# Adafruit_BNO055.net
KiCad netlist of a schematic drawn in EAGLE
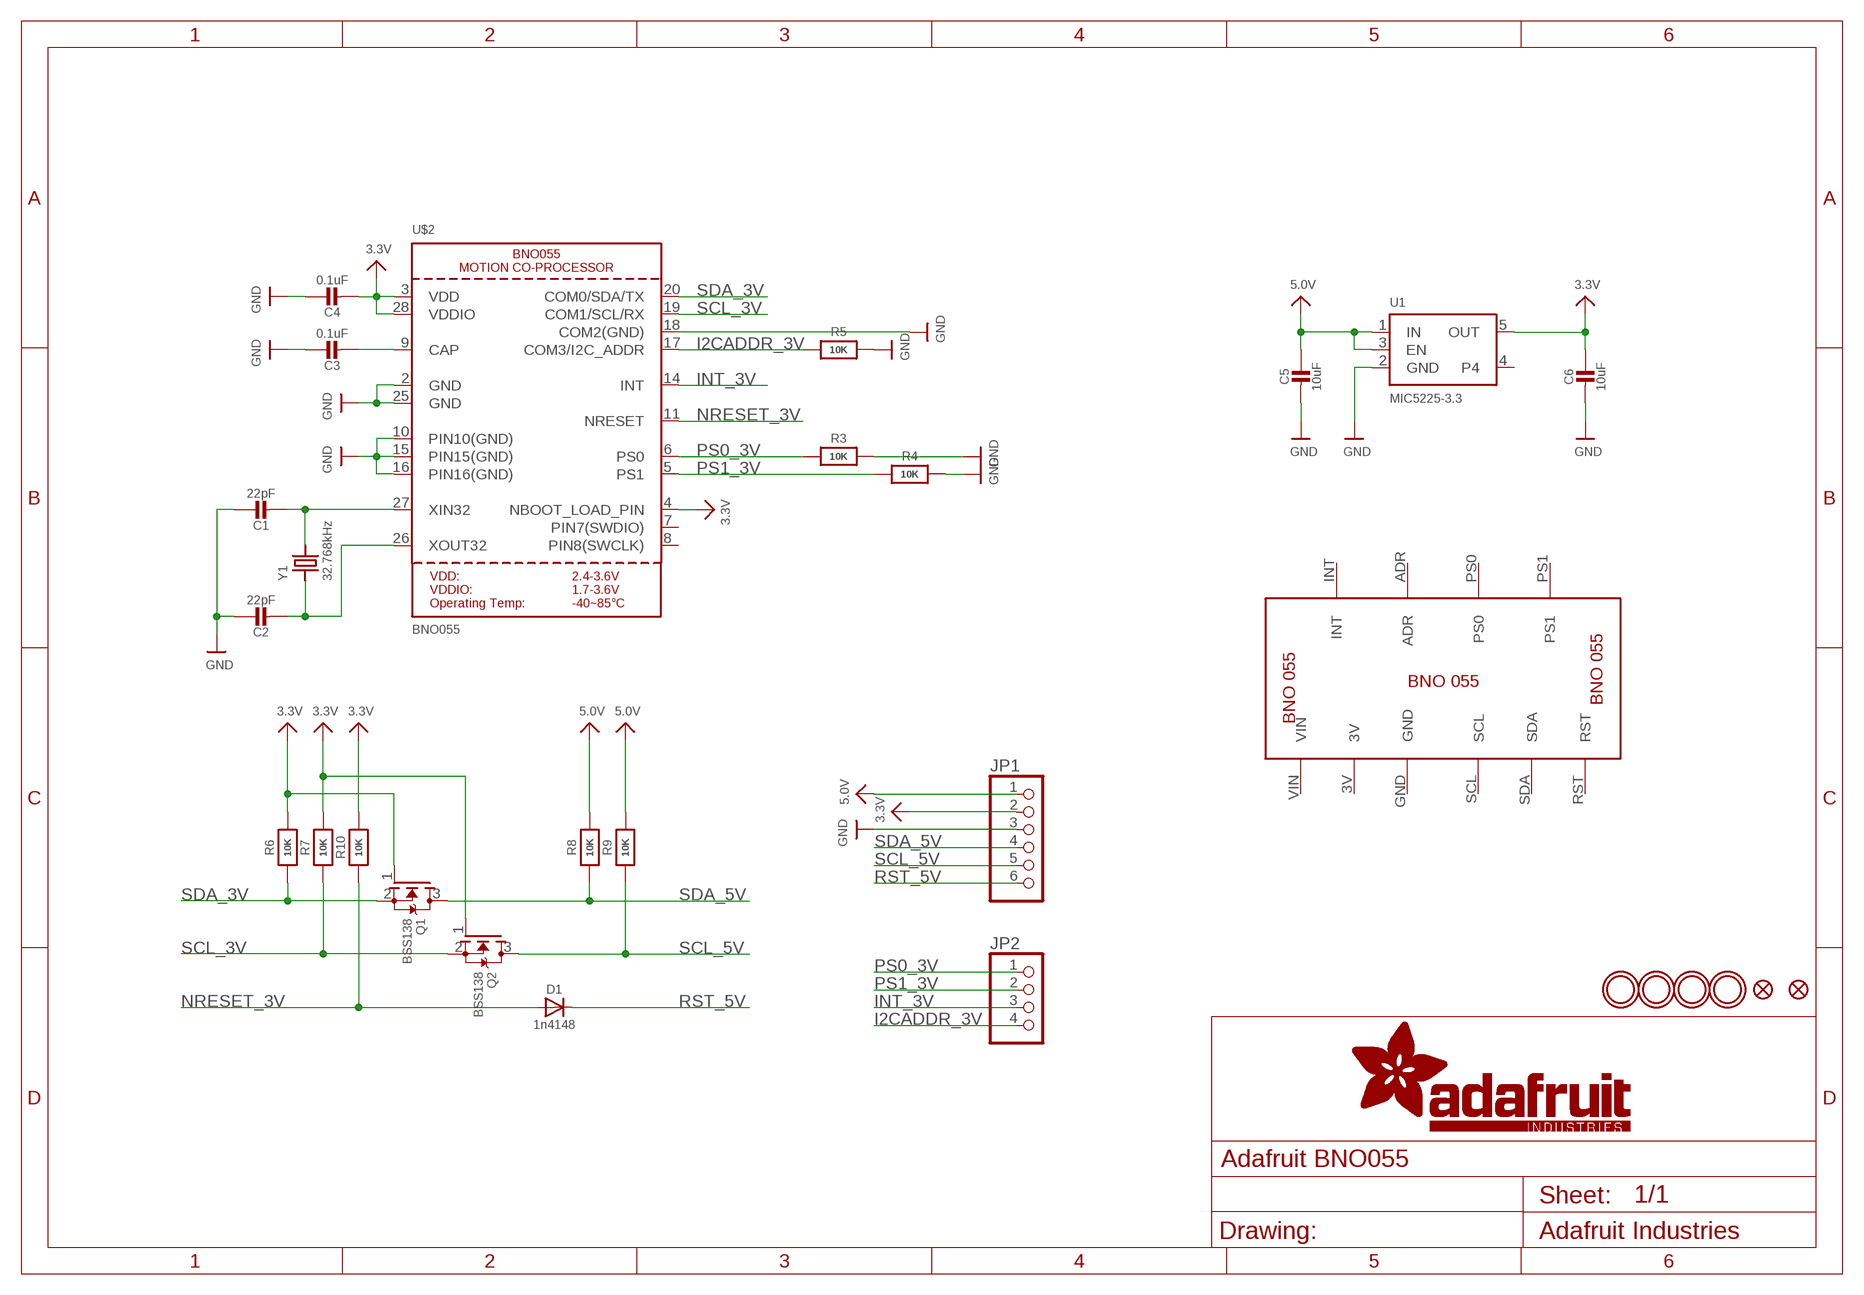
[diagram p0: schematic, sheet 1]

(export (version "E")
  (design (tool "Eeschema 10.0.6"))
  (components
    (comp (ref "C1")
      (value "22pF")
      (footprint "eagle-import:0805-NO")
      (libsource (lib "eagle-import") (part "CAP_CERAMIC0805-NOOUTLINE"))
    )
    (comp (ref "C2")
      (value "22pF")
      (footprint "eagle-import:0805-NO")
      (libsource (lib "eagle-import") (part "CAP_CERAMIC0805-NOOUTLINE"))
    )
    (comp (ref "C3")
      (value "0.1uF")
      (footprint "eagle-import:0805-NO")
      (libsource (lib "eagle-import") (part "CAP_CERAMIC0805-NOOUTLINE"))
    )
    (comp (ref "C4")
      (value "0.1uF")
      (footprint "eagle-import:0805_10MGAP")
      (libsource (lib "eagle-import") (part "CAP_CERAMIC0805_10MGAP"))
    )
    (comp (ref "C5")
      (value "10uF")
      (footprint "eagle-import:0805-NO")
      (libsource (lib "eagle-import") (part "CAP_CERAMIC0805-NOOUTLINE"))
    )
    (comp (ref "C6")
      (value "10uF")
      (footprint "eagle-import:0805_10MGAP")
      (libsource (lib "eagle-import") (part "CAP_CERAMIC0805_10MGAP"))
    )
    (comp (ref "D1")
      (value "1n4148")
      (footprint "eagle-import:SOD-323")
      (libsource (lib "eagle-import") (part "DIODESOD-323"))
    )
    (comp (ref "FID1")
      (value "FIDUCIAL\"\"")
      (footprint "eagle-import:FIDUCIAL_1MM")
      (libsource (lib "eagle-import") (part "FIDUCIAL{dblquote}{dblquote}"))
    )
    (comp (ref "FID2")
      (value "FIDUCIAL\"\"")
      (footprint "eagle-import:FIDUCIAL_1MM")
      (libsource (lib "eagle-import") (part "FIDUCIAL{dblquote}{dblquote}"))
    )
    (comp (ref "JP1")
      (value "HEADER-1X676MIL")
      (footprint "eagle-import:1X06_ROUND_76")
      (libsource (lib "eagle-import") (part "HEADER-1X676MIL"))
    )
    (comp (ref "JP2")
      (value "HEADER-1X476MIL")
      (footprint "eagle-import:1X04_ROUND_76")
      (libsource (lib "eagle-import") (part "HEADER-1X476MIL"))
    )
    (comp (ref "Q1")
      (value "BSS138")
      (footprint "eagle-import:SOT23-WIDE")
      (libsource (lib "eagle-import") (part "MOSFET-NWIDE"))
    )
    (comp (ref "Q2")
      (value "BSS138")
      (footprint "eagle-import:SOT23-WIDE")
      (libsource (lib "eagle-import") (part "MOSFET-NWIDE"))
    )
    (comp (ref "R3")
      (value "10K")
      (footprint "eagle-import:0805-NO")
      (libsource (lib "eagle-import") (part "RESISTOR0805_NOOUTLINE"))
    )
    (comp (ref "R4")
      (value "10K")
      (footprint "eagle-import:0805-NO")
      (libsource (lib "eagle-import") (part "RESISTOR0805_NOOUTLINE"))
    )
    (comp (ref "R5")
      (value "10K")
      (footprint "eagle-import:0805-NO")
      (libsource (lib "eagle-import") (part "RESISTOR0805_NOOUTLINE"))
    )
    (comp (ref "R6")
      (value "10K")
      (footprint "eagle-import:0805-NO")
      (libsource (lib "eagle-import") (part "RESISTOR0805_NOOUTLINE"))
    )
    (comp (ref "R7")
      (value "10K")
      (footprint "eagle-import:0805-NO")
      (libsource (lib "eagle-import") (part "RESISTOR0805_NOOUTLINE"))
    )
    (comp (ref "R8")
      (value "10K")
      (footprint "eagle-import:_0805MP")
      (libsource (lib "eagle-import") (part "RESISTOR_0805MP"))
    )
    (comp (ref "R9")
      (value "10K")
      (footprint "eagle-import:_0805MP")
      (libsource (lib "eagle-import") (part "RESISTOR_0805MP"))
    )
    (comp (ref "R10")
      (value "10K")
      (footprint "eagle-import:0805-NO")
      (libsource (lib "eagle-import") (part "RESISTOR0805_NOOUTLINE"))
    )
    (comp (ref "U$2")
      (value "BNO055")
      (footprint "eagle-import:BNO055")
      (libsource (lib "eagle-import") (part "microbuilder_BNO055"))
    )
    (comp (ref "U$29")
      (value "MOUNTINGHOLE2.5_THICK")
      (footprint "eagle-import:MOUNTINGHOLE_2.5_PLATED_THICK")
      (libsource (lib "eagle-import") (part "MOUNTINGHOLE2.5_THICK"))
    )
    (comp (ref "U$30")
      (value "MOUNTINGHOLE2.5_THICK")
      (footprint "eagle-import:MOUNTINGHOLE_2.5_PLATED_THICK")
      (libsource (lib "eagle-import") (part "MOUNTINGHOLE2.5_THICK"))
    )
    (comp (ref "U$31")
      (value "MOUNTINGHOLE2.5_THICK")
      (footprint "eagle-import:MOUNTINGHOLE_2.5_PLATED_THICK")
      (libsource (lib "eagle-import") (part "MOUNTINGHOLE2.5_THICK"))
    )
    (comp (ref "U$32")
      (value "MOUNTINGHOLE2.5_THICK")
      (footprint "eagle-import:MOUNTINGHOLE_2.5_PLATED_THICK")
      (libsource (lib "eagle-import") (part "MOUNTINGHOLE2.5_THICK"))
    )
    (comp (ref "U$34")
      (value "BNO055")
      (footprint "eagle-import:BNO055")
      (libsource (lib "eagle-import") (part "BNO055"))
    )
    (comp (ref "U1")
      (value "MIC5225-3.3")
      (footprint "eagle-import:SOT23-5")
      (libsource (lib "eagle-import") (part "VREG_SOT23-5"))
    )
    (comp (ref "Y1")
      (value "32.768kHz")
      (footprint "eagle-import:CRYSTAL_8X3.8")
      (libsource (lib "eagle-import") (part "CRYSTAL8.0X3.8"))
    )
  )
  (nets
    (net (code "1") (name "/I2CADDR_3V") (class "Default")
      (node (ref "JP2") (pin "4") (pinfunction "4_4") (pintype "passive"))
      (node (ref "R5") (pin "1") (pinfunction "1_1") (pintype "passive"))
      (node (ref "U$2") (pin "17") (pinfunction "COM3/I2C_ADDR_17") (pintype "bidirectional"))
    )
    (net (code "2") (name "/INT_3V") (class "Default")
      (node (ref "JP2") (pin "3") (pinfunction "3_3") (pintype "passive"))
      (node (ref "U$2") (pin "14") (pinfunction "INT_14") (pintype "output"))
    )
    (net (code "3") (name "/NRESET_3V") (class "Default")
      (node (ref "D1") (pin "A") (pinfunction "A_A") (pintype "passive"))
      (node (ref "R10") (pin "1") (pinfunction "1_1") (pintype "passive"))
      (node (ref "U$2") (pin "11") (pinfunction "NRESET_11") (pintype "bidirectional"))
    )
    (net (code "4") (name "/PS0_3V") (class "Default")
      (node (ref "JP2") (pin "1") (pinfunction "1_1") (pintype "passive"))
      (node (ref "R3") (pin "1") (pinfunction "1_1") (pintype "passive"))
      (node (ref "U$2") (pin "6") (pinfunction "PS0_6") (pintype "input"))
    )
    (net (code "5") (name "/PS1_3V") (class "Default")
      (node (ref "JP2") (pin "2") (pinfunction "2_2") (pintype "passive"))
      (node (ref "R4") (pin "1") (pinfunction "1_1") (pintype "passive"))
      (node (ref "U$2") (pin "5") (pinfunction "PS1_5") (pintype "input"))
    )
    (net (code "6") (name "/RST_5V") (class "Default")
      (node (ref "D1") (pin "C") (pinfunction "C_C") (pintype "passive"))
      (node (ref "JP1") (pin "6") (pinfunction "6_6") (pintype "passive"))
    )
    (net (code "7") (name "/SCL_3V") (class "Default")
      (node (ref "Q2") (pin "2") (pinfunction "S_2") (pintype "bidirectional"))
      (node (ref "R7") (pin "1") (pinfunction "1_1") (pintype "passive"))
      (node (ref "U$2") (pin "19") (pinfunction "COM1/SCL/RX_19") (pintype "bidirectional"))
    )
    (net (code "8") (name "/SCL_5V") (class "Default")
      (node (ref "JP1") (pin "5") (pinfunction "5_5") (pintype "passive"))
      (node (ref "Q2") (pin "3") (pinfunction "D_3") (pintype "bidirectional"))
      (node (ref "R9") (pin "1") (pinfunction "1_1") (pintype "passive"))
    )
    (net (code "9") (name "/SDA_3V") (class "Default")
      (node (ref "Q1") (pin "2") (pinfunction "S_2") (pintype "bidirectional"))
      (node (ref "R6") (pin "1") (pinfunction "1_1") (pintype "passive"))
      (node (ref "U$2") (pin "20") (pinfunction "COM0/SDA/TX_20") (pintype "bidirectional"))
    )
    (net (code "10") (name "/SDA_5V") (class "Default")
      (node (ref "JP1") (pin "4") (pinfunction "4_4") (pintype "passive"))
      (node (ref "Q1") (pin "3") (pinfunction "D_3") (pintype "bidirectional"))
      (node (ref "R8") (pin "1") (pinfunction "1_1") (pintype "passive"))
    )
    (net (code "11") (name "3.3V") (class "Default")
      (node (ref "C4") (pin "2") (pinfunction "2_2") (pintype "passive"))
      (node (ref "C6") (pin "1") (pinfunction "1_1") (pintype "passive"))
      (node (ref "JP1") (pin "2") (pinfunction "2_2") (pintype "passive"))
      (node (ref "Q1") (pin "1") (pinfunction "G_1") (pintype "bidirectional"))
      (node (ref "Q2") (pin "1") (pinfunction "G_1") (pintype "bidirectional"))
      (node (ref "R10") (pin "2") (pinfunction "2_2") (pintype "passive"))
      (node (ref "R6") (pin "2") (pinfunction "2_2") (pintype "passive"))
      (node (ref "R7") (pin "2") (pinfunction "2_2") (pintype "passive"))
      (node (ref "U$2") (pin "28") (pinfunction "VDDIO_28") (pintype "power_in"))
      (node (ref "U$2") (pin "3") (pinfunction "VDD_3") (pintype "power_in"))
      (node (ref "U$2") (pin "4") (pinfunction "NBOOT_LOAD_PIN_4") (pintype "bidirectional"))
      (node (ref "U1") (pin "5") (pinfunction "OUT_5") (pintype "power_in"))
    )
    (net (code "12") (name "5.0V") (class "Default")
      (node (ref "C5") (pin "1") (pinfunction "1_1") (pintype "passive"))
      (node (ref "JP1") (pin "1") (pinfunction "1_1") (pintype "passive"))
      (node (ref "R8") (pin "2") (pinfunction "2_2") (pintype "passive"))
      (node (ref "R9") (pin "2") (pinfunction "2_2") (pintype "passive"))
      (node (ref "U1") (pin "1") (pinfunction "IN_1") (pintype "power_in"))
      (node (ref "U1") (pin "3") (pinfunction "EN_3") (pintype "input"))
    )
    (net (code "13") (name "GND") (class "Default")
      (node (ref "C1") (pin "1") (pinfunction "1_1") (pintype "passive"))
      (node (ref "C2") (pin "1") (pinfunction "1_1") (pintype "passive"))
      (node (ref "C3") (pin "1") (pinfunction "1_1") (pintype "passive"))
      (node (ref "C4") (pin "1") (pinfunction "1_1") (pintype "passive"))
      (node (ref "C5") (pin "2") (pinfunction "2_2") (pintype "passive"))
      (node (ref "C6") (pin "2") (pinfunction "2_2") (pintype "passive"))
      (node (ref "JP1") (pin "3") (pinfunction "3_3") (pintype "passive"))
      (node (ref "R3") (pin "2") (pinfunction "2_2") (pintype "passive"))
      (node (ref "R4") (pin "2") (pinfunction "2_2") (pintype "passive"))
      (node (ref "R5") (pin "2") (pinfunction "2_2") (pintype "passive"))
      (node (ref "U$2") (pin "10") (pinfunction "PIN10(GND)_10") (pintype "bidirectional"))
      (node (ref "U$2") (pin "15") (pinfunction "PIN15(GND)_15") (pintype "bidirectional"))
      (node (ref "U$2") (pin "16") (pinfunction "PIN16(GND)_16") (pintype "bidirectional"))
      (node (ref "U$2") (pin "18") (pinfunction "COM2(GND)_18") (pintype "bidirectional"))
      (node (ref "U$2") (pin "2") (pinfunction "GND_2") (pintype "power_in"))
      (node (ref "U$2") (pin "25") (pinfunction "GND_25") (pintype "power_in"))
      (node (ref "U1") (pin "2") (pinfunction "GND_2") (pintype "power_in"))
    )
    (net (code "14") (name "Net-(U$2-CAP)") (class "Default")
      (node (ref "C3") (pin "2") (pinfunction "2_2") (pintype "passive"))
      (node (ref "U$2") (pin "9") (pinfunction "CAP_9") (pintype "passive"))
    )
    (net (code "15") (name "Net-(U$2-XIN32)") (class "Default")
      (node (ref "C1") (pin "2") (pinfunction "2_2") (pintype "passive"))
      (node (ref "U$2") (pin "27") (pinfunction "XIN32_27") (pintype "input"))
      (node (ref "Y1") (pin "P$4") (pinfunction "2_P$4") (pintype "passive"))
    )
    (net (code "16") (name "Net-(U$2-XOUT32)") (class "Default")
      (node (ref "C2") (pin "2") (pinfunction "2_2") (pintype "passive"))
      (node (ref "U$2") (pin "26") (pinfunction "XOUT32_26") (pintype "output"))
      (node (ref "Y1") (pin "P$1") (pinfunction "1_P$1") (pintype "passive"))
    )
    (net (code "17") (name "unconnected-(U$2-PIN7(SWDIO)-Pad7)") (class "Default")
      (node (ref "U$2") (pin "7") (pinfunction "PIN7(SWDIO)_7") (pintype "bidirectional"))
    )
    (net (code "18") (name "unconnected-(U$2-PIN8(SWCLK)-Pad8)") (class "Default")
      (node (ref "U$2") (pin "8") (pinfunction "PIN8(SWCLK)_8") (pintype "bidirectional"))
    )
    (net (code "19") (name "unconnected-(U$34-Pad3V)") (class "Default")
      (node (ref "U$34") (pin "3V") (pinfunction "3V_3V") (pintype "bidirectional"))
    )
    (net (code "20") (name "unconnected-(U$34-PadADR)") (class "Default")
      (node (ref "U$34") (pin "ADR") (pinfunction "ADR_ADR") (pintype "bidirectional"))
    )
    (net (code "21") (name "unconnected-(U$34-PadGND)") (class "Default")
      (node (ref "U$34") (pin "GND") (pinfunction "GND_GND") (pintype "bidirectional"))
    )
    (net (code "22") (name "unconnected-(U$34-PadINT)") (class "Default")
      (node (ref "U$34") (pin "INT") (pinfunction "INT_INT") (pintype "bidirectional"))
    )
    (net (code "23") (name "unconnected-(U$34-PadPS0)") (class "Default")
      (node (ref "U$34") (pin "PS0") (pinfunction "PS0_PS0") (pintype "bidirectional"))
    )
    (net (code "24") (name "unconnected-(U$34-PadPS1)") (class "Default")
      (node (ref "U$34") (pin "PS1") (pinfunction "PS1_PS1") (pintype "bidirectional"))
    )
    (net (code "25") (name "unconnected-(U$34-PadRST)") (class "Default")
      (node (ref "U$34") (pin "RST") (pinfunction "RST_RST") (pintype "bidirectional"))
    )
    (net (code "26") (name "unconnected-(U$34-PadSCL)") (class "Default")
      (node (ref "U$34") (pin "SCL") (pinfunction "SCL_SCL") (pintype "bidirectional"))
    )
    (net (code "27") (name "unconnected-(U$34-PadSDA)") (class "Default")
      (node (ref "U$34") (pin "SDA") (pinfunction "SDA_SDA") (pintype "bidirectional"))
    )
    (net (code "28") (name "unconnected-(U$34-PadVIN)") (class "Default")
      (node (ref "U$34") (pin "VIN") (pinfunction "VIN_VIN") (pintype "bidirectional"))
    )
    (net (code "29") (name "unconnected-(U1-P4-Pad4)") (class "Default")
      (node (ref "U1") (pin "4") (pinfunction "P4_4") (pintype "bidirectional"))
    )
  )
)
